# MCU_IO.net
KiCad netlist of a schematic drawn in Altium Designer
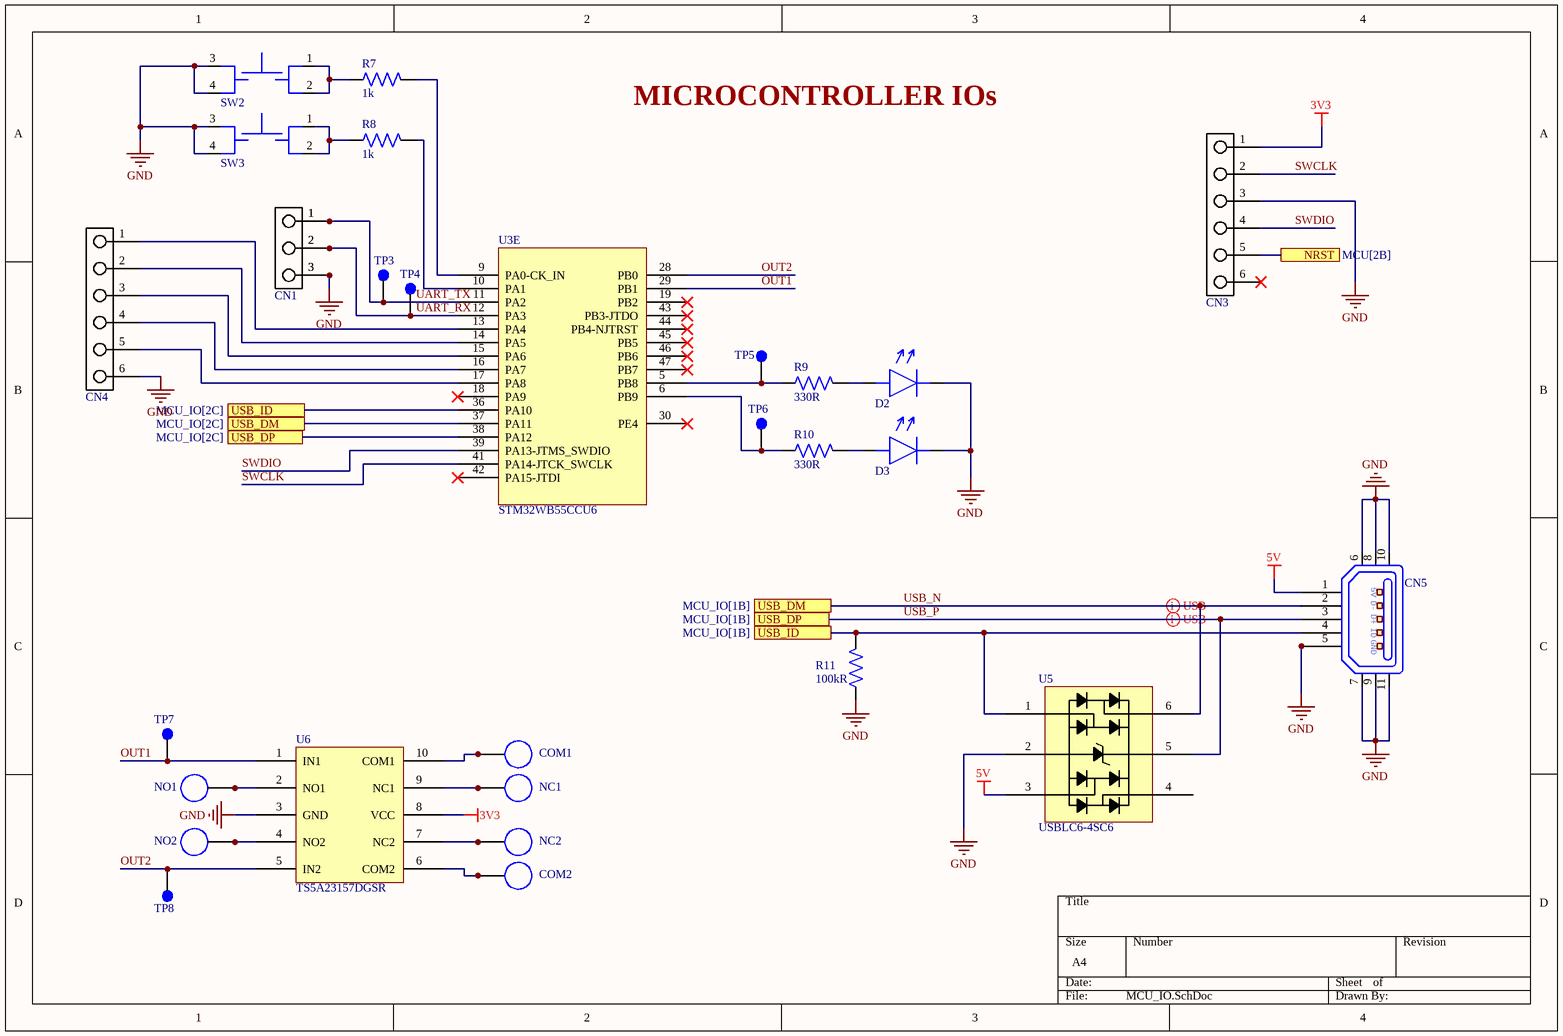
[diagram p0: MCU_IO.SchDoc]

(export (version "E")
  (design (tool "Eeschema 10.0.6"))
  (components
    (comp (ref "CN1")
      (value "1x3 Header")
      (footprint "1x3Header")
      (libsource (lib "Schlib1") (part "1x3 Header"))
    )
    (comp (ref "CN3")
      (value "SSW-106-22-F-S-VS")
      (footprint "SSW-106-22-F-S-VS-K-TR")
      (description "Conn Socket Strip SKT 6 POS 2.54mm Solder ST SMD Tube")
      (fields (field (name "MANUFACTURER") "Samtec"))
      (libsource (lib "Schlib1") (part "SSW-106-22-F-S-VS"))
    )
    (comp (ref "CN4")
      (value "90147-1306")
      (footprint "1x6Header")
      (description "Header Connector, pcb Mount, plug, 6 Contacts, skt, 0.1 Pitch, pc Tail Terminal ¦Molex 90147-1306")
      (fields (field (name "MANUFACTURER") "Molex"))
      (libsource (lib "Schlib1") (part "90147-1306"))
    )
    (comp (ref "CN5")
      (value "MUSB-05-F-AB-SM-A-K")
      (footprint "USB")
      (description "\"Mini USB 2.0 Interface\"")
      (fields (field (name "MANUFACTURER") "Samtec"))
      (libsource (lib "Schlib1") (part "MUSB-05-F-AB-SM-A-K"))
    )
    (comp (ref "COM1")
      (value "Terminal")
      (footprint "2.5mmHOLE")
      (libsource (lib "Schlib1") (part "Terminal"))
    )
    (comp (ref "COM2")
      (value "Terminal")
      (footprint "2.5mmHOLE")
      (libsource (lib "Schlib1") (part "Terminal"))
    )
    (comp (ref "D2")
      (value "HSMS-C680")
      (footprint "LED")
      (description "LED Uni-Color Red 636nm 2-Pin Chip LED T/R")
      (fields (field (name "MANUFACTURER") "Broadcom Avago"))
      (libsource (lib "Schlib1") (part "HSMS-C680"))
    )
    (comp (ref "D3")
      (value "HSMS-C680")
      (footprint "LED")
      (description "LED Uni-Color Red 636nm 2-Pin Chip LED T/R")
      (fields (field (name "MANUFACTURER") "Broadcom Avago"))
      (libsource (lib "Schlib1") (part "HSMS-C680"))
    )
    (comp (ref "NC1")
      (value "Terminal")
      (footprint "2.5mmHOLE")
      (libsource (lib "Schlib1") (part "Terminal"))
    )
    (comp (ref "NC2")
      (value "Terminal")
      (footprint "2.5mmHOLE")
      (libsource (lib "Schlib1") (part "Terminal"))
    )
    (comp (ref "NO1")
      (value "Terminal")
      (footprint "2.5mmHOLE")
      (libsource (lib "Schlib1") (part "Terminal"))
    )
    (comp (ref "NO2")
      (value "Terminal")
      (footprint "2.5mmHOLE")
      (libsource (lib "Schlib1") (part "Terminal"))
    )
    (comp (ref "R7")
      (value "1k")
      (footprint "R0402")
      (description "SMD Chip Resistor 1 Kohm ½ 1% 62.5 Mw 0402 [1005 Metric] Thick Film General Purpose")
      (fields
        (field (name "MANUFACTURER") "Yageo")
        (field (name "MANUFACTURER PART NUMBER") "RC0402FR-071KL")
      )
      (libsource (lib "Schlib1") (part "RC0402FR-071KL"))
    )
    (comp (ref "R8")
      (value "1k")
      (footprint "R0402")
      (description "SMD Chip Resistor 1 Kohm ½ 1% 62.5 Mw 0402 [1005 Metric] Thick Film General Purpose")
      (fields
        (field (name "MANUFACTURER") "Yageo")
        (field (name "MANUFACTURER PART NUMBER") "RC0402FR-071KL")
      )
      (libsource (lib "Schlib1") (part "RC0402FR-071KL"))
    )
    (comp (ref "R9")
      (value "330R")
      (footprint "R0402")
      (description "Res Thick Film 0402 330 Ohm 5% 1/16W ±100ppm/°C Molded SMD SMD Paper T/R")
      (fields
        (field (name "MANUFACTURER") "Yageo")
        (field (name "MANUFACTURER PART NUMBER") "RC0402JR-13330RL")
      )
      (libsource (lib "Schlib1") (part "RC0402JR-13330RL"))
    )
    (comp (ref "R10")
      (value "330R")
      (footprint "R0402")
      (description "Res Thick Film 0402 330 Ohm 5% 1/16W ±100ppm/°C Molded SMD SMD Paper T/R")
      (fields
        (field (name "MANUFACTURER") "Yageo")
        (field (name "MANUFACTURER PART NUMBER") "RC0402JR-13330RL")
      )
      (libsource (lib "Schlib1") (part "RC0402JR-13330RL"))
    )
    (comp (ref "R11")
      (value "100kR")
      (footprint "R0402")
      (description "SMD Chip Resistor, 100 Kohm, ½ 5%, 62.5 Mw, 0402 [1005 Metric], Thick Film, General Purpose")
      (fields
        (field (name "MANUFACTURER") "Yageo")
        (field (name "MANUFACTURER PART NUMBER") "RC0402JR-07100KL")
      )
      (libsource (lib "Schlib1") (part "RC0402JR-07100KL"))
    )
    (comp (ref "SW2")
      (value "TS02-66-130-BK-260-LCR-D")
      (footprint "BUTTON")
      (fields (field (name "MANUFACTURER") "Same Sky"))
      (libsource (lib "Schlib1") (part "TS02-66-130-BK-260-LCR-D"))
    )
    (comp (ref "SW3")
      (value "TS02-66-130-BK-260-LCR-D")
      (footprint "BUTTON")
      (fields (field (name "MANUFACTURER") "Same Sky"))
      (libsource (lib "Schlib1") (part "TS02-66-130-BK-260-LCR-D"))
    )
    (comp (ref "TP3")
      (value "TP")
      (footprint "TP")
      (description "Test Point")
      (libsource (lib "Schlib1") (part "TP"))
    )
    (comp (ref "TP4")
      (value "TP")
      (footprint "TP")
      (description "Test Point")
      (libsource (lib "Schlib1") (part "TP"))
    )
    (comp (ref "TP5")
      (value "TP")
      (footprint "TP")
      (description "Test Point")
      (libsource (lib "Schlib1") (part "TP"))
    )
    (comp (ref "TP6")
      (value "TP")
      (footprint "TP")
      (description "Test Point")
      (libsource (lib "Schlib1") (part "TP"))
    )
    (comp (ref "TP7")
      (value "TP")
      (footprint "TP")
      (description "Test Point")
      (libsource (lib "Schlib1") (part "TP"))
    )
    (comp (ref "TP8")
      (value "TP")
      (footprint "TP")
      (description "Test Point")
      (libsource (lib "Schlib1") (part "TP"))
    )
    (comp (ref "U3")
      (value "STM32WB55CCU6")
      (footprint "WB55")
      (description "MCU 32-Bit STM32WB55 ARM Cortex-M4F RISC 256KB Flash 1.71V to 3.6V 48-Pin UFQFPN T/R")
      (fields (field (name "MANUFACTURER") "STMicroelectronics"))
      (libsource (lib "Schlib1") (part "STM32WB55CCU6"))
    )
    (comp (ref "U5")
      (value "USBLC6-4SC6")
      (footprint "SOT23-6")
      (description "USBLC6 Series 4 Line 6 V Uni / Bi-Directional ESD Protection - SOT-23-6")
      (fields (field (name "MANUFACTURER") "STMicroelectronics"))
      (libsource (lib "Schlib1") (part "USBLC6-4SC6"))
    )
    (comp (ref "U6")
      (value "TS5A23157DGSR")
      (footprint "VSSOP10")
      (description "Integrated Circuit Analog Switch; 5-V, 2: 1 (SPDT), 2-channel analog switch 10-VSSOP -40 to 125")
      (fields (field (name "MANUFACTURER") "Texas Instruments"))
      (libsource (lib "Schlib1") (part "TS5A23157DGSR"))
    )
  )
  (nets
    (net (code "1") (name "/NRST") (class "Default")
      (node (ref "CN3") (pin "5") (pinfunction "5_5") (pintype "passive"))
    )
    (net (code "2") (name "/OUT1") (class "Default")
      (node (ref "TP7") (pin "1") (pinfunction "1_1") (pintype "passive"))
      (node (ref "U3") (pin "29") (pinfunction "PB1_29") (pintype "passive"))
      (node (ref "U6") (pin "1") (pinfunction "IN1_1") (pintype "passive"))
    )
    (net (code "3") (name "/OUT2") (class "Default")
      (node (ref "TP8") (pin "1") (pinfunction "1_1") (pintype "passive"))
      (node (ref "U3") (pin "28") (pinfunction "PB0_28") (pintype "passive"))
      (node (ref "U6") (pin "5") (pinfunction "IN2_5") (pintype "passive"))
    )
    (net (code "4") (name "/SWCLK") (class "Default")
      (node (ref "CN3") (pin "2") (pinfunction "2_2") (pintype "passive"))
      (node (ref "U3") (pin "41") (pinfunction "PA14-JTCK_SWCLK_41") (pintype "passive"))
    )
    (net (code "5") (name "/SWDIO") (class "Default")
      (node (ref "CN3") (pin "4") (pinfunction "4_4") (pintype "passive"))
      (node (ref "U3") (pin "39") (pinfunction "PA13-JTMS_SWDIO_39") (pintype "passive"))
    )
    (net (code "6") (name "/UART_RX") (class "Default")
      (node (ref "CN1") (pin "2") (pinfunction "2_2") (pintype "passive"))
      (node (ref "TP4") (pin "1") (pinfunction "1_1") (pintype "passive"))
      (node (ref "U3") (pin "12") (pinfunction "PA3_12") (pintype "passive"))
    )
    (net (code "7") (name "/UART_TX") (class "Default")
      (node (ref "CN1") (pin "1") (pinfunction "1_1") (pintype "passive"))
      (node (ref "TP3") (pin "1") (pinfunction "1_1") (pintype "passive"))
      (node (ref "U3") (pin "11") (pinfunction "PA2_11") (pintype "passive"))
    )
    (net (code "8") (name "/USB_ID") (class "Default")
      (node (ref "CN5") (pin "4") (pinfunction "4_4") (pintype "passive"))
      (node (ref "R11") (pin "2") (pinfunction "2_2") (pintype "passive"))
      (node (ref "U3") (pin "36") (pinfunction "PA10_36") (pintype "passive"))
      (node (ref "U5") (pin "1") (pinfunction "1_1") (pintype "passive"))
    )
    (net (code "9") (name "/USB_N") (class "Default")
      (node (ref "CN5") (pin "2") (pinfunction "2_2") (pintype "passive"))
      (node (ref "U3") (pin "37") (pinfunction "PA11_37") (pintype "passive"))
      (node (ref "U5") (pin "6") (pinfunction "6_6") (pintype "passive"))
    )
    (net (code "10") (name "/USB_P") (class "Default")
      (node (ref "CN5") (pin "3") (pinfunction "3_3") (pintype "passive"))
      (node (ref "U3") (pin "38") (pinfunction "PA12_38") (pintype "passive"))
      (node (ref "U5") (pin "5") (pinfunction "5_5") (pintype "passive"))
    )
    (net (code "11") (name "3V3") (class "Default")
      (node (ref "CN3") (pin "1") (pinfunction "1_1") (pintype "passive"))
      (node (ref "U6") (pin "8") (pinfunction "VCC_8") (pintype "passive"))
    )
    (net (code "12") (name "5V") (class "Default")
      (node (ref "CN5") (pin "1") (pinfunction "1_1") (pintype "passive"))
      (node (ref "U5") (pin "3") (pinfunction "3_3") (pintype "passive"))
    )
    (net (code "13") (name "GND") (class "Default")
      (node (ref "CN1") (pin "3") (pinfunction "3_3") (pintype "passive"))
      (node (ref "CN3") (pin "3") (pinfunction "3_3") (pintype "passive"))
      (node (ref "CN4") (pin "6") (pinfunction "6_6") (pintype "passive"))
      (node (ref "CN5") (pin "10") (pinfunction "10_10") (pintype "passive"))
      (node (ref "CN5") (pin "11") (pinfunction "11_11") (pintype "passive"))
      (node (ref "CN5") (pin "5") (pinfunction "5_5") (pintype "passive"))
      (node (ref "CN5") (pin "6") (pinfunction "6_6") (pintype "passive"))
      (node (ref "CN5") (pin "7") (pinfunction "7_7") (pintype "passive"))
      (node (ref "CN5") (pin "8") (pinfunction "8_8") (pintype "passive"))
      (node (ref "CN5") (pin "9") (pinfunction "9_9") (pintype "passive"))
      (node (ref "D2") (pin "2") (pinfunction "2_2") (pintype "passive"))
      (node (ref "D3") (pin "2") (pinfunction "2_2") (pintype "passive"))
      (node (ref "R11") (pin "1") (pinfunction "1_1") (pintype "passive"))
      (node (ref "SW2") (pin "3") (pinfunction "3_3") (pintype "passive"))
      (node (ref "SW2") (pin "4") (pinfunction "4_4") (pintype "passive"))
      (node (ref "SW3") (pin "3") (pinfunction "3_3") (pintype "passive"))
      (node (ref "SW3") (pin "4") (pinfunction "4_4") (pintype "passive"))
      (node (ref "U5") (pin "2") (pinfunction "GND_2") (pintype "passive"))
      (node (ref "U6") (pin "3") (pinfunction "GND_3") (pintype "passive"))
    )
    (net (code "14") (name "Net-(D2-Pad1)") (class "Default")
      (node (ref "D2") (pin "1") (pinfunction "1_1") (pintype "passive"))
      (node (ref "R9") (pin "2") (pinfunction "2_2") (pintype "passive"))
    )
    (net (code "15") (name "Net-(D3-Pad1)") (class "Default")
      (node (ref "D3") (pin "1") (pinfunction "1_1") (pintype "passive"))
      (node (ref "R10") (pin "2") (pinfunction "2_2") (pintype "passive"))
    )
    (net (code "16") (name "Net-(R7-Pad1)") (class "Default")
      (node (ref "R7") (pin "1") (pinfunction "1_1") (pintype "passive"))
      (node (ref "SW2") (pin "1") (pinfunction "1_1") (pintype "passive"))
      (node (ref "SW2") (pin "2") (pinfunction "2_2") (pintype "passive"))
    )
    (net (code "17") (name "Net-(R8-Pad1)") (class "Default")
      (node (ref "R8") (pin "1") (pinfunction "1_1") (pintype "passive"))
      (node (ref "SW3") (pin "1") (pinfunction "1_1") (pintype "passive"))
      (node (ref "SW3") (pin "2") (pinfunction "2_2") (pintype "passive"))
    )
    (net (code "18") (name "Net-(U3E-PA0-CK_IN)") (class "Default")
      (node (ref "R7") (pin "2") (pinfunction "2_2") (pintype "passive"))
      (node (ref "U3") (pin "9") (pinfunction "PA0-CK_IN_9") (pintype "passive"))
    )
    (net (code "19") (name "Net-(U3E-PA1)") (class "Default")
      (node (ref "R8") (pin "2") (pinfunction "2_2") (pintype "passive"))
      (node (ref "U3") (pin "10") (pinfunction "PA1_10") (pintype "passive"))
    )
    (net (code "20") (name "Net-(U3E-PA4)") (class "Default")
      (node (ref "CN4") (pin "1") (pinfunction "1_1") (pintype "passive"))
      (node (ref "U3") (pin "13") (pinfunction "PA4_13") (pintype "passive"))
    )
    (net (code "21") (name "Net-(U3E-PA5)") (class "Default")
      (node (ref "CN4") (pin "2") (pinfunction "2_2") (pintype "passive"))
      (node (ref "U3") (pin "14") (pinfunction "PA5_14") (pintype "passive"))
    )
    (net (code "22") (name "Net-(U3E-PA6)") (class "Default")
      (node (ref "CN4") (pin "3") (pinfunction "3_3") (pintype "passive"))
      (node (ref "U3") (pin "15") (pinfunction "PA6_15") (pintype "passive"))
    )
    (net (code "23") (name "Net-(U3E-PA7)") (class "Default")
      (node (ref "CN4") (pin "4") (pinfunction "4_4") (pintype "passive"))
      (node (ref "U3") (pin "16") (pinfunction "PA7_16") (pintype "passive"))
    )
    (net (code "24") (name "Net-(U3E-PA8)") (class "Default")
      (node (ref "CN4") (pin "5") (pinfunction "5_5") (pintype "passive"))
      (node (ref "U3") (pin "17") (pinfunction "PA8_17") (pintype "passive"))
    )
    (net (code "25") (name "Net-(U3E-PB8)") (class "Default")
      (node (ref "R9") (pin "1") (pinfunction "1_1") (pintype "passive"))
      (node (ref "TP5") (pin "1") (pinfunction "1_1") (pintype "passive"))
      (node (ref "U3") (pin "5") (pinfunction "PB8_5") (pintype "passive"))
    )
    (net (code "26") (name "Net-(U3E-PB9)") (class "Default")
      (node (ref "R10") (pin "1") (pinfunction "1_1") (pintype "passive"))
      (node (ref "TP6") (pin "1") (pinfunction "1_1") (pintype "passive"))
      (node (ref "U3") (pin "6") (pinfunction "PB9_6") (pintype "passive"))
    )
    (net (code "27") (name "Net-(U6-COM1)") (class "Default")
      (node (ref "COM1") (pin "1") (pinfunction "1_1") (pintype "passive"))
      (node (ref "U6") (pin "10") (pinfunction "COM1_10") (pintype "passive"))
    )
    (net (code "28") (name "Net-(U6-COM2)") (class "Default")
      (node (ref "COM2") (pin "1") (pinfunction "1_1") (pintype "passive"))
      (node (ref "U6") (pin "6") (pinfunction "COM2_6") (pintype "passive"))
    )
    (net (code "29") (name "Net-(U6-NC1)") (class "Default")
      (node (ref "NC1") (pin "1") (pinfunction "1_1") (pintype "passive"))
      (node (ref "U6") (pin "9") (pinfunction "NC1_9") (pintype "passive"))
    )
    (net (code "30") (name "Net-(U6-NC2)") (class "Default")
      (node (ref "NC2") (pin "1") (pinfunction "1_1") (pintype "passive"))
      (node (ref "U6") (pin "7") (pinfunction "NC2_7") (pintype "passive"))
    )
    (net (code "31") (name "Net-(U6-NO1)") (class "Default")
      (node (ref "NO1") (pin "1") (pinfunction "1_1") (pintype "passive"))
      (node (ref "U6") (pin "2") (pinfunction "NO1_2") (pintype "passive"))
    )
    (net (code "32") (name "Net-(U6-NO2)") (class "Default")
      (node (ref "NO2") (pin "1") (pinfunction "1_1") (pintype "passive"))
      (node (ref "U6") (pin "4") (pinfunction "NO2_4") (pintype "passive"))
    )
    (net (code "33") (name "unconnected-(CN3-Pad6)") (class "Default")
      (node (ref "CN3") (pin "6") (pinfunction "6_6") (pintype "passive+no_connect"))
    )
    (net (code "34") (name "unconnected-(U3E-PA9-Pad18)") (class "Default")
      (node (ref "U3") (pin "18") (pinfunction "PA9_18") (pintype "passive+no_connect"))
    )
    (net (code "35") (name "unconnected-(U3E-PA15-JTDI-Pad42)") (class "Default")
      (node (ref "U3") (pin "42") (pinfunction "PA15-JTDI_42") (pintype "passive+no_connect"))
    )
    (net (code "36") (name "unconnected-(U3E-PB2-Pad19)") (class "Default")
      (node (ref "U3") (pin "19") (pinfunction "PB2_19") (pintype "passive+no_connect"))
    )
    (net (code "37") (name "unconnected-(U3E-PB3-JTDO-Pad43)") (class "Default")
      (node (ref "U3") (pin "43") (pinfunction "PB3-JTDO_43") (pintype "passive+no_connect"))
    )
    (net (code "38") (name "unconnected-(U3E-PB4-NJTRST-Pad44)") (class "Default")
      (node (ref "U3") (pin "44") (pinfunction "PB4-NJTRST_44") (pintype "passive+no_connect"))
    )
    (net (code "39") (name "unconnected-(U3E-PB5-Pad45)") (class "Default")
      (node (ref "U3") (pin "45") (pinfunction "PB5_45") (pintype "passive+no_connect"))
    )
    (net (code "40") (name "unconnected-(U3E-PB6-Pad46)") (class "Default")
      (node (ref "U3") (pin "46") (pinfunction "PB6_46") (pintype "passive+no_connect"))
    )
    (net (code "41") (name "unconnected-(U3E-PB7-Pad47)") (class "Default")
      (node (ref "U3") (pin "47") (pinfunction "PB7_47") (pintype "passive+no_connect"))
    )
    (net (code "42") (name "unconnected-(U3E-PE4-Pad30)") (class "Default")
      (node (ref "U3") (pin "30") (pinfunction "PE4_30") (pintype "passive+no_connect"))
    )
    (net (code "43") (name "unconnected-(U5-Pad4)") (class "Default")
      (node (ref "U5") (pin "4") (pinfunction "4_4") (pintype "passive"))
    )
  )
)
